# 2211B_SysArrosageAuto_MCU.net
KiCad netlist of a schematic drawn in Altium Designer
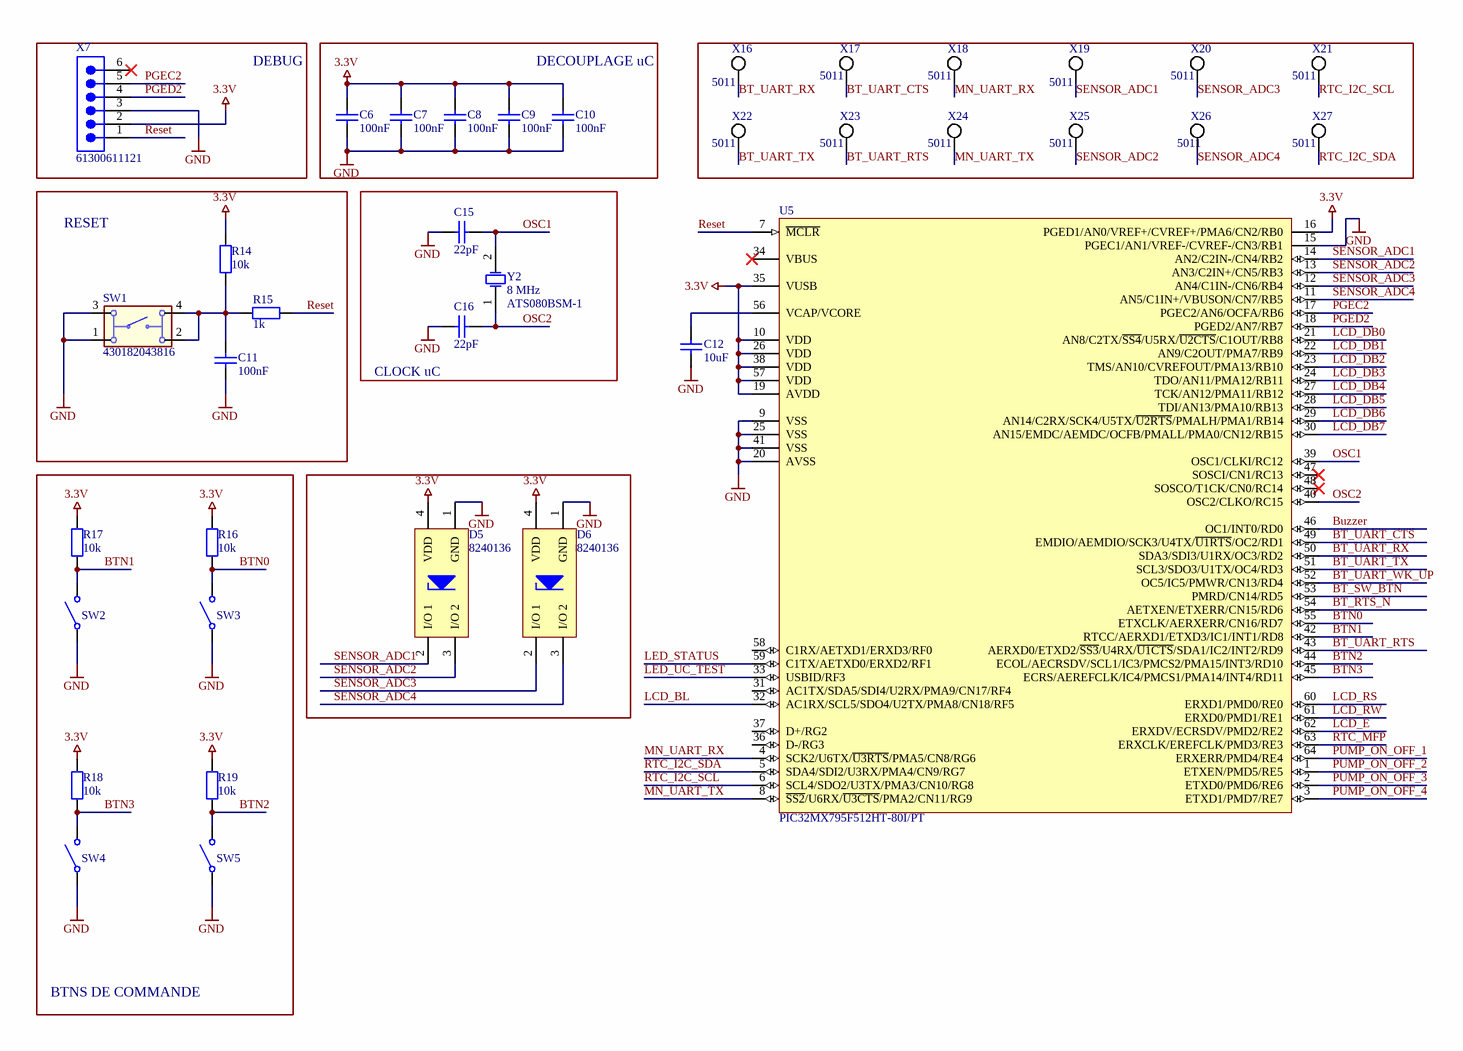
[diagram p0: 2211B_SysArrosageAuto_MCU.SchDoc, right]

(export (version "E")
  (design (tool "Eeschema 10.0.6"))
  (components
    (comp (ref "C6")
      (value "100nF")
      (footprint "CAPC2013X145X48NL20T23")
      (libsource (lib "Sys_Arossage") (part "Capacitor_Non-Polarized"))
    )
    (comp (ref "C7")
      (value "100nF")
      (footprint "CAPC2013X145X48NL20T23")
      (libsource (lib "Sys_Arossage") (part "Capacitor_Non-Polarized"))
    )
    (comp (ref "C8")
      (value "100nF")
      (footprint "CAPC2013X145X48NL20T23")
      (libsource (lib "Sys_Arossage") (part "Capacitor_Non-Polarized"))
    )
    (comp (ref "C9")
      (value "100nF")
      (footprint "CAPC2013X145X48NL20T23")
      (libsource (lib "Sys_Arossage") (part "Capacitor_Non-Polarized"))
    )
    (comp (ref "C10")
      (value "100nF")
      (footprint "CAPC2013X145X48NL20T23")
      (libsource (lib "Sys_Arossage") (part "Capacitor_Non-Polarized"))
    )
    (comp (ref "C11")
      (value "100nF")
      (footprint "CAPC2013X145X48NL20T23")
      (libsource (lib "Sys_Arossage") (part "Capacitor_Non-Polarized"))
    )
    (comp (ref "C12")
      (value "10uF")
      (footprint "CAPC2013X145X48NL20T23")
      (libsource (lib "Sys_Arossage") (part "Capacitor_Non-Polarized"))
    )
    (comp (ref "C15")
      (value "22pF")
      (footprint "CAPC2013X145X48NL20T23")
      (libsource (lib "Sys_Arossage") (part "Capacitor_Non-Polarized"))
    )
    (comp (ref "C16")
      (value "22pF")
      (footprint "CAPC2013X145X48NL20T23")
      (libsource (lib "Sys_Arossage") (part "Capacitor_Non-Polarized"))
    )
    (comp (ref "D5")
      (value "8240136")
      (footprint "WE-TVS_SOT143-4L")
      (libsource (lib "Sys_Arossage") (part "CMP-1486-00002-2"))
    )
    (comp (ref "D6")
      (value "8240136")
      (footprint "WE-TVS_SOT143-4L")
      (libsource (lib "Sys_Arossage") (part "CMP-1486-00002-2"))
    )
    (comp (ref "R14")
      (value "10k")
      (footprint "RESC2012X60N")
      (description "SMD Chip Resistor, 10 kOhm, ± 1%, 125 mW, 0805 [2012 Metric], Thick Film, General Purpose")
      (fields
        (field (name "MANUFACTURER") "Yageo")
        (field (name "MANUFACTURER PART NUMBER") "RC0805FR-0710KL")
      )
      (libsource (lib "Sys_Arossage") (part "R-SMD"))
    )
    (comp (ref "R15")
      (value "1k")
      (footprint "RESC2012X60N")
      (description "SMD Chip Resistor, 10 kOhm, ± 1%, 125 mW, 0805 [2012 Metric], Thick Film, General Purpose")
      (fields
        (field (name "MANUFACTURER") "Yageo")
        (field (name "MANUFACTURER PART NUMBER") "RC0805FR-0710KL")
      )
      (libsource (lib "") (part "R-SMD_1"))
    )
    (comp (ref "R16")
      (value "10k")
      (footprint "RESC2012X60N")
      (description "SMD Chip Resistor, 10 kOhm, ± 1%, 125 mW, 0805 [2012 Metric], Thick Film, General Purpose")
      (fields
        (field (name "MANUFACTURER") "Yageo")
        (field (name "MANUFACTURER PART NUMBER") "RC0805FR-0710KL")
      )
      (libsource (lib "Sys_Arossage") (part "R-SMD"))
    )
    (comp (ref "R17")
      (value "10k")
      (footprint "RESC2012X60N")
      (description "SMD Chip Resistor, 10 kOhm, ± 1%, 125 mW, 0805 [2012 Metric], Thick Film, General Purpose")
      (fields
        (field (name "MANUFACTURER") "Yageo")
        (field (name "MANUFACTURER PART NUMBER") "RC0805FR-0710KL")
      )
      (libsource (lib "Sys_Arossage") (part "R-SMD"))
    )
    (comp (ref "R18")
      (value "10k")
      (footprint "RESC2012X60N")
      (description "SMD Chip Resistor, 10 kOhm, ± 1%, 125 mW, 0805 [2012 Metric], Thick Film, General Purpose")
      (fields
        (field (name "MANUFACTURER") "Yageo")
        (field (name "MANUFACTURER PART NUMBER") "RC0805FR-0710KL")
      )
      (libsource (lib "Sys_Arossage") (part "R-SMD"))
    )
    (comp (ref "R19")
      (value "10k")
      (footprint "RESC2012X60N")
      (description "SMD Chip Resistor, 10 kOhm, ± 1%, 125 mW, 0805 [2012 Metric], Thick Film, General Purpose")
      (fields
        (field (name "MANUFACTURER") "Yageo")
        (field (name "MANUFACTURER PART NUMBER") "RC0805FR-0710KL")
      )
      (libsource (lib "Sys_Arossage") (part "R-SMD"))
    )
    (comp (ref "SW1")
      (value "430182043816")
      (footprint "SOIC_82043816_WRE-L")
      (description "Switch Tactile N.O. SPST Round Button Gull Wing 0.05A 12VDC 1000000Cycles 1.57N SMD Reel")
      (fields (field (name "MANUFACTURER") "Wurth Electronics"))
      (libsource (lib "Sys_Arossage") (part "SWITCH_SPST-NO"))
    )
    (comp (ref "SW2")
      (value "Single-Pole,Single-Throw Switch")
      (footprint "61300211121")
      (libsource (lib "Sys_Arossage") (part "SPST SW"))
    )
    (comp (ref "SW3")
      (value "Single-Pole,Single-Throw Switch")
      (footprint "61300211121")
      (libsource (lib "Sys_Arossage") (part "SPST SW"))
    )
    (comp (ref "SW4")
      (value "Single-Pole,Single-Throw Switch")
      (footprint "61300211121")
      (libsource (lib "Sys_Arossage") (part "SPST SW"))
    )
    (comp (ref "SW5")
      (value "Single-Pole,Single-Throw Switch")
      (footprint "61300211121")
      (libsource (lib "Sys_Arossage") (part "SPST SW"))
    )
    (comp (ref "U5")
      (value "PIC32MX795F512HT-80I/PT")
      (footprint "TQFP-PT64_L")
      (libsource (lib "Sys_Arossage") (part "CMP-0048-00048-2"))
    )
    (comp (ref "X7")
      (value "61300611121")
      (footprint "61300611121")
      (description "THT Vertical Pin Header WR-PHD, Pitch 2.54 mm, Single Row, 6 pins")
      (fields (field (name "MANUFACTURER") "Wurth Electronics"))
      (libsource (lib "Sys_Arossage") (part "CMP-1502-01068-2_1"))
    )
    (comp (ref "X16")
      (value "5011")
      (footprint "Keystone_5011")
      (fields (field (name "MANUFACTURER") "Keystone") (field (name "MANUFACTURER_1") "Keystone Electronics"))
      (libsource (lib "Sys_Arossage") (part "TEST_POINT_THT"))
    )
    (comp (ref "X17")
      (value "5011")
      (footprint "Keystone_5011")
      (fields (field (name "MANUFACTURER") "Keystone") (field (name "MANUFACTURER_1") "Keystone Electronics"))
      (libsource (lib "Sys_Arossage") (part "TEST_POINT_THT"))
    )
    (comp (ref "X18")
      (value "5011")
      (footprint "Keystone_5011")
      (fields (field (name "MANUFACTURER") "Keystone") (field (name "MANUFACTURER_1") "Keystone Electronics"))
      (libsource (lib "Sys_Arossage") (part "TEST_POINT_THT"))
    )
    (comp (ref "X19")
      (value "5011")
      (footprint "Keystone_5011")
      (fields (field (name "MANUFACTURER") "Keystone") (field (name "MANUFACTURER_1") "Keystone Electronics"))
      (libsource (lib "Sys_Arossage") (part "TEST_POINT_THT"))
    )
    (comp (ref "X20")
      (value "5011")
      (footprint "Keystone_5011")
      (fields (field (name "MANUFACTURER") "Keystone") (field (name "MANUFACTURER_1") "Keystone Electronics"))
      (libsource (lib "Sys_Arossage") (part "TEST_POINT_THT"))
    )
    (comp (ref "X21")
      (value "5011")
      (footprint "Keystone_5011")
      (fields (field (name "MANUFACTURER") "Keystone") (field (name "MANUFACTURER_1") "Keystone Electronics"))
      (libsource (lib "Sys_Arossage") (part "TEST_POINT_THT"))
    )
    (comp (ref "X22")
      (value "5011")
      (footprint "Keystone_5011")
      (fields (field (name "MANUFACTURER") "Keystone") (field (name "MANUFACTURER_1") "Keystone Electronics"))
      (libsource (lib "Sys_Arossage") (part "TEST_POINT_THT"))
    )
    (comp (ref "X23")
      (value "5011")
      (footprint "Keystone_5011")
      (fields (field (name "MANUFACTURER") "Keystone") (field (name "MANUFACTURER_1") "Keystone Electronics"))
      (libsource (lib "Sys_Arossage") (part "TEST_POINT_THT"))
    )
    (comp (ref "X24")
      (value "5011")
      (footprint "Keystone_5011")
      (fields (field (name "MANUFACTURER") "Keystone") (field (name "MANUFACTURER_1") "Keystone Electronics"))
      (libsource (lib "Sys_Arossage") (part "TEST_POINT_THT"))
    )
    (comp (ref "X25")
      (value "5011")
      (footprint "Keystone_5011")
      (fields (field (name "MANUFACTURER") "Keystone") (field (name "MANUFACTURER_1") "Keystone Electronics"))
      (libsource (lib "Sys_Arossage") (part "TEST_POINT_THT"))
    )
    (comp (ref "X26")
      (value "5011")
      (footprint "Keystone_5011")
      (fields (field (name "MANUFACTURER") "Keystone") (field (name "MANUFACTURER_1") "Keystone Electronics"))
      (libsource (lib "Sys_Arossage") (part "TEST_POINT_THT"))
    )
    (comp (ref "X27")
      (value "5011")
      (footprint "Keystone_5011")
      (fields (field (name "MANUFACTURER") "Keystone") (field (name "MANUFACTURER_1") "Keystone Electronics"))
      (libsource (lib "Sys_Arossage") (part "TEST_POINT_THT"))
    )
    (comp (ref "Y2")
      (value "8 MHz")
      (footprint "ATS080BSM-1")
      (description "Crystal 8MHz ±30ppm (Tol) ±50ppm (Stability) 18pF FUND 60Ohm 2-Pin HC-49/US SM SMD T/R")
      (fields
        (field (name "MANUFACTURER") "CTS")
        (field (name "MANUFACTURER PART NUMBER") "ATS080BSM-1")
        (field (name "SUPPLIER PART NUMBER 1") "ATS080BSM-1")
        (field (name "PUBLISHER") "Altium Limited")
      )
      (libsource (lib "Sys_Arossage") (part "XTAL"))
    )
  )
  (nets
    (net (code "1") (name "/BTN0") (class "Default")
      (node (ref "R16") (pin "1") (pinfunction "1_1") (pintype "passive"))
      (node (ref "SW3") (pin "2") (pinfunction "2_2") (pintype "passive"))
      (node (ref "U5") (pin "55") (pinfunction "ETXCLK/AERXERR/CN16/RD7_55") (pintype "bidirectional"))
    )
    (net (code "2") (name "/BTN1") (class "Default")
      (node (ref "R17") (pin "1") (pinfunction "1_1") (pintype "passive"))
      (node (ref "SW2") (pin "2") (pinfunction "2_2") (pintype "passive"))
      (node (ref "U5") (pin "42") (pinfunction "RTCC/AERXD1/ETXD3/IC1/INT1/RD8_42") (pintype "bidirectional"))
    )
    (net (code "3") (name "/BTN2") (class "Default")
      (node (ref "R19") (pin "1") (pinfunction "1_1") (pintype "passive"))
      (node (ref "SW5") (pin "2") (pinfunction "2_2") (pintype "passive"))
      (node (ref "U5") (pin "44") (pinfunction "ECOL/AECRSDV/SCL1/IC3/PMCS2/PMA15/INT3/RD10_44") (pintype "bidirectional"))
    )
    (net (code "4") (name "/BTN3") (class "Default")
      (node (ref "R18") (pin "1") (pinfunction "1_1") (pintype "passive"))
      (node (ref "SW4") (pin "2") (pinfunction "2_2") (pintype "passive"))
      (node (ref "U5") (pin "45") (pinfunction "ECRS/AEREFCLK/IC4/PMCS1/PMA14/INT4/RD11_45") (pintype "bidirectional"))
    )
    (net (code "5") (name "/BT_RTS_N") (class "Default")
      (node (ref "U5") (pin "54") (pinfunction "AETXEN/ETXERR/CN15/RD6_54") (pintype "bidirectional"))
    )
    (net (code "6") (name "/BT_SW_BTN") (class "Default")
      (node (ref "U5") (pin "53") (pinfunction "PMRD/CN14/RD5_53") (pintype "bidirectional"))
    )
    (net (code "7") (name "/BT_UART_CTS") (class "Default")
      (node (ref "U5") (pin "49") (pinfunction "EMDIO/AEMDIO/SCK3/U4TX/~{U1RTS}/OC2/RD1_49") (pintype "bidirectional"))
      (node (ref "X17") (pin "1") (pinfunction "TP_1") (pintype "passive"))
    )
    (net (code "8") (name "/BT_UART_RTS") (class "Default")
      (node (ref "U5") (pin "43") (pinfunction "AERXD0/ETXD2/~{SS3}/U4RX/~{U1CTS}/SDA1/IC2/INT2/RD9_43") (pintype "bidirectional"))
      (node (ref "X23") (pin "1") (pinfunction "TP_1") (pintype "passive"))
    )
    (net (code "9") (name "/BT_UART_RX") (class "Default")
      (node (ref "U5") (pin "50") (pinfunction "SDA3/SDI3/U1RX/OC3/RD2_50") (pintype "bidirectional"))
      (node (ref "X16") (pin "1") (pinfunction "TP_1") (pintype "passive"))
    )
    (net (code "10") (name "/BT_UART_TX") (class "Default")
      (node (ref "U5") (pin "51") (pinfunction "SCL3/SDO3/U1TX/OC4/RD3_51") (pintype "bidirectional"))
      (node (ref "X22") (pin "1") (pinfunction "TP_1") (pintype "passive"))
    )
    (net (code "11") (name "/BT_UART_WK_UP") (class "Default")
      (node (ref "U5") (pin "52") (pinfunction "OC5/IC5/PMWR/CN13/RD4_52") (pintype "bidirectional"))
    )
    (net (code "12") (name "/Buzzer") (class "Default")
      (node (ref "U5") (pin "46") (pinfunction "OC1/INT0/RD0_46") (pintype "bidirectional"))
    )
    (net (code "13") (name "/LCD_BL") (class "Default")
      (node (ref "U5") (pin "32") (pinfunction "AC1RX/SCL5/SDO4/U2TX/PMA8/CN18/RF5_32") (pintype "bidirectional"))
    )
    (net (code "14") (name "/LCD_DB0") (class "Default")
      (node (ref "U5") (pin "21") (pinfunction "AN8/C2TX/~{SS4}/U5RX/~{U2CTS}/C1OUT/RB8_21") (pintype "bidirectional"))
    )
    (net (code "15") (name "/LCD_DB1") (class "Default")
      (node (ref "U5") (pin "22") (pinfunction "AN9/C2OUT/PMA7/RB9_22") (pintype "bidirectional"))
    )
    (net (code "16") (name "/LCD_DB2") (class "Default")
      (node (ref "U5") (pin "23") (pinfunction "TMS/AN10/CVREFOUT/PMA13/RB10_23") (pintype "bidirectional"))
    )
    (net (code "17") (name "/LCD_DB3") (class "Default")
      (node (ref "U5") (pin "24") (pinfunction "TDO/AN11/PMA12/RB11_24") (pintype "bidirectional"))
    )
    (net (code "18") (name "/LCD_DB4") (class "Default")
      (node (ref "U5") (pin "27") (pinfunction "TCK/AN12/PMA11/RB12_27") (pintype "bidirectional"))
    )
    (net (code "19") (name "/LCD_DB5") (class "Default")
      (node (ref "U5") (pin "28") (pinfunction "TDI/AN13/PMA10/RB13_28") (pintype "bidirectional"))
    )
    (net (code "20") (name "/LCD_DB6") (class "Default")
      (node (ref "U5") (pin "29") (pinfunction "AN14/C2RX/SCK4/U5TX/~{U2RTS}/PMALH/PMA1/RB14_29") (pintype "bidirectional"))
    )
    (net (code "21") (name "/LCD_DB7") (class "Default")
      (node (ref "U5") (pin "30") (pinfunction "AN15/EMDC/AEMDC/OCFB/PMALL/PMA0/CN12/RB15_30") (pintype "bidirectional"))
    )
    (net (code "22") (name "/LCD_E") (class "Default")
      (node (ref "U5") (pin "62") (pinfunction "ERXDV/ECRSDV/PMD2/RE2_62") (pintype "bidirectional"))
    )
    (net (code "23") (name "/LCD_RS") (class "Default")
      (node (ref "U5") (pin "60") (pinfunction "ERXD1/PMD0/RE0_60") (pintype "bidirectional"))
    )
    (net (code "24") (name "/LCD_RW") (class "Default")
      (node (ref "U5") (pin "61") (pinfunction "ERXD0/PMD1/RE1_61") (pintype "bidirectional"))
    )
    (net (code "25") (name "/LED_STATUS") (class "Default")
      (node (ref "U5") (pin "59") (pinfunction "C1TX/AETXD0/ERXD2/RF1_59") (pintype "bidirectional"))
    )
    (net (code "26") (name "/LED_UC_TEST") (class "Default")
      (node (ref "U5") (pin "33") (pinfunction "USBID/RF3_33") (pintype "bidirectional"))
    )
    (net (code "27") (name "/MN_UART_RX") (class "Default")
      (node (ref "U5") (pin "4") (pinfunction "SCK2/U6TX/~{U3RTS}/PMA5/CN8/RG6_4") (pintype "bidirectional"))
      (node (ref "X18") (pin "1") (pinfunction "TP_1") (pintype "passive"))
    )
    (net (code "28") (name "/MN_UART_TX") (class "Default")
      (node (ref "U5") (pin "8") (pinfunction "~{SS2}/U6RX/~{U3CTS}/PMA2/CN11/RG9_8") (pintype "bidirectional"))
      (node (ref "X24") (pin "1") (pinfunction "TP_1") (pintype "passive"))
    )
    (net (code "29") (name "/OSC1") (class "Default")
      (node (ref "C15") (pin "2") (pinfunction "2_2") (pintype "passive"))
      (node (ref "U5") (pin "39") (pinfunction "OSC1/CLKI/RC12_39") (pintype "bidirectional"))
      (node (ref "Y2") (pin "2") (pinfunction "OSC2_2") (pintype "passive"))
    )
    (net (code "30") (name "/OSC2") (class "Default")
      (node (ref "C16") (pin "2") (pinfunction "2_2") (pintype "passive"))
      (node (ref "U5") (pin "40") (pinfunction "OSC2/CLKO/RC15_40") (pintype "bidirectional"))
      (node (ref "Y2") (pin "1") (pinfunction "OSC1_1") (pintype "passive"))
    )
    (net (code "31") (name "/PGEC2") (class "Default")
      (node (ref "U5") (pin "17") (pinfunction "PGEC2/AN6/OCFA/RB6_17") (pintype "bidirectional"))
      (node (ref "X7") (pin "5") (pinfunction "5_5") (pintype "passive"))
    )
    (net (code "32") (name "/PGED2") (class "Default")
      (node (ref "U5") (pin "18") (pinfunction "PGED2/AN7/RB7_18") (pintype "bidirectional"))
      (node (ref "X7") (pin "4") (pinfunction "4_4") (pintype "passive"))
    )
    (net (code "33") (name "/PUMP_ON_OFF_1") (class "Default")
      (node (ref "U5") (pin "64") (pinfunction "ERXERR/PMD4/RE4_64") (pintype "bidirectional"))
    )
    (net (code "34") (name "/PUMP_ON_OFF_2") (class "Default")
      (node (ref "U5") (pin "1") (pinfunction "ETXEN/PMD5/RE5_1") (pintype "bidirectional"))
    )
    (net (code "35") (name "/PUMP_ON_OFF_3") (class "Default")
      (node (ref "U5") (pin "2") (pinfunction "ETXD0/PMD6/RE6_2") (pintype "bidirectional"))
    )
    (net (code "36") (name "/PUMP_ON_OFF_4") (class "Default")
      (node (ref "U5") (pin "3") (pinfunction "ETXD1/PMD7/RE7_3") (pintype "bidirectional"))
    )
    (net (code "37") (name "/RTC_I2C_SCL") (class "Default")
      (node (ref "U5") (pin "6") (pinfunction "SCL4/SDO2/U3TX/PMA3/CN10/RG8_6") (pintype "bidirectional"))
      (node (ref "X21") (pin "1") (pinfunction "TP_1") (pintype "passive"))
    )
    (net (code "38") (name "/RTC_I2C_SDA") (class "Default")
      (node (ref "U5") (pin "5") (pinfunction "SDA4/SDI2/U3RX/PMA4/CN9/RG7_5") (pintype "bidirectional"))
      (node (ref "X27") (pin "1") (pinfunction "TP_1") (pintype "passive"))
    )
    (net (code "39") (name "/RTC_MFP") (class "Default")
      (node (ref "U5") (pin "63") (pinfunction "ERXCLK/EREFCLK/PMD3/RE3_63") (pintype "bidirectional"))
    )
    (net (code "40") (name "/Reset") (class "Default")
      (node (ref "R15") (pin "2") (pinfunction "2_2") (pintype "passive"))
      (node (ref "U5") (pin "7") (pinfunction "~{MCLR}_7") (pintype "input"))
      (node (ref "X7") (pin "1") (pinfunction "1_1") (pintype "passive"))
    )
    (net (code "41") (name "/SENSOR_ADC1") (class "Default")
      (node (ref "D5") (pin "2") (pinfunction "I/O_1_2") (pintype "passive"))
      (node (ref "U5") (pin "14") (pinfunction "AN2/C2IN-/CN4/RB2_14") (pintype "bidirectional"))
      (node (ref "X19") (pin "1") (pinfunction "TP_1") (pintype "passive"))
    )
    (net (code "42") (name "/SENSOR_ADC2") (class "Default")
      (node (ref "D5") (pin "3") (pinfunction "I/O_2_3") (pintype "passive"))
      (node (ref "U5") (pin "13") (pinfunction "AN3/C2IN+/CN5/RB3_13") (pintype "bidirectional"))
      (node (ref "X25") (pin "1") (pinfunction "TP_1") (pintype "passive"))
    )
    (net (code "43") (name "/SENSOR_ADC3") (class "Default")
      (node (ref "D6") (pin "2") (pinfunction "I/O_1_2") (pintype "passive"))
      (node (ref "U5") (pin "12") (pinfunction "AN4/C1IN-/CN6/RB4_12") (pintype "bidirectional"))
      (node (ref "X20") (pin "1") (pinfunction "TP_1") (pintype "passive"))
    )
    (net (code "44") (name "/SENSOR_ADC4") (class "Default")
      (node (ref "D6") (pin "3") (pinfunction "I/O_2_3") (pintype "passive"))
      (node (ref "U5") (pin "11") (pinfunction "AN5/C1IN+/VBUSON/CN7/RB5_11") (pintype "bidirectional"))
      (node (ref "X26") (pin "1") (pinfunction "TP_1") (pintype "passive"))
    )
    (net (code "45") (name "3.3V") (class "Default")
      (node (ref "C10") (pin "2") (pinfunction "2_2") (pintype "passive"))
      (node (ref "C6") (pin "2") (pinfunction "2_2") (pintype "passive"))
      (node (ref "C7") (pin "2") (pinfunction "2_2") (pintype "passive"))
      (node (ref "C8") (pin "2") (pinfunction "2_2") (pintype "passive"))
      (node (ref "C9") (pin "2") (pinfunction "2_2") (pintype "passive"))
      (node (ref "D5") (pin "4") (pinfunction "VDD_4") (pintype "passive"))
      (node (ref "D6") (pin "4") (pinfunction "VDD_4") (pintype "passive"))
      (node (ref "R14") (pin "2") (pinfunction "2_2") (pintype "passive"))
      (node (ref "R16") (pin "2") (pinfunction "2_2") (pintype "passive"))
      (node (ref "R17") (pin "2") (pinfunction "2_2") (pintype "passive"))
      (node (ref "R18") (pin "2") (pinfunction "2_2") (pintype "passive"))
      (node (ref "R19") (pin "2") (pinfunction "2_2") (pintype "passive"))
      (node (ref "U5") (pin "10") (pinfunction "VDD_10") (pintype "passive"))
      (node (ref "U5") (pin "16") (pinfunction "PGED1/AN0/VREF+/CVREF+/PMA6/CN2/RB0_16") (pintype "power_in"))
      (node (ref "U5") (pin "19") (pinfunction "AVDD_19") (pintype "passive"))
      (node (ref "U5") (pin "26") (pinfunction "VDD_26") (pintype "passive"))
      (node (ref "U5") (pin "35") (pinfunction "VUSB_35") (pintype "passive"))
      (node (ref "U5") (pin "38") (pinfunction "VDD_38") (pintype "passive"))
      (node (ref "U5") (pin "57") (pinfunction "VDD_57") (pintype "passive"))
      (node (ref "X7") (pin "2") (pinfunction "2_2") (pintype "passive"))
    )
    (net (code "46") (name "GND") (class "Default")
      (node (ref "C10") (pin "1") (pinfunction "1_1") (pintype "passive"))
      (node (ref "C11") (pin "1") (pinfunction "1_1") (pintype "passive"))
      (node (ref "C12") (pin "1") (pinfunction "1_1") (pintype "passive"))
      (node (ref "C15") (pin "1") (pinfunction "1_1") (pintype "passive"))
      (node (ref "C16") (pin "1") (pinfunction "1_1") (pintype "passive"))
      (node (ref "C6") (pin "1") (pinfunction "1_1") (pintype "passive"))
      (node (ref "C7") (pin "1") (pinfunction "1_1") (pintype "passive"))
      (node (ref "C8") (pin "1") (pinfunction "1_1") (pintype "passive"))
      (node (ref "C9") (pin "1") (pinfunction "1_1") (pintype "passive"))
      (node (ref "D5") (pin "1") (pinfunction "GND_1") (pintype "passive"))
      (node (ref "D6") (pin "1") (pinfunction "GND_1") (pintype "passive"))
      (node (ref "SW1") (pin "1") (pinfunction "1_1") (pintype "passive"))
      (node (ref "SW1") (pin "3") (pinfunction "3_3") (pintype "passive"))
      (node (ref "SW2") (pin "1") (pinfunction "1_1") (pintype "passive"))
      (node (ref "SW3") (pin "1") (pinfunction "1_1") (pintype "passive"))
      (node (ref "SW4") (pin "1") (pinfunction "1_1") (pintype "passive"))
      (node (ref "SW5") (pin "1") (pinfunction "1_1") (pintype "passive"))
      (node (ref "U5") (pin "15") (pinfunction "PGEC1/AN1/VREF-/CVREF-/CN3/RB1_15") (pintype "power_in"))
      (node (ref "U5") (pin "20") (pinfunction "AVSS_20") (pintype "passive"))
      (node (ref "U5") (pin "25") (pinfunction "VSS_25") (pintype "passive"))
      (node (ref "U5") (pin "41") (pinfunction "VSS_41") (pintype "passive"))
      (node (ref "U5") (pin "9") (pinfunction "VSS_9") (pintype "passive"))
      (node (ref "X7") (pin "3") (pinfunction "3_3") (pintype "passive"))
    )
    (net (code "47") (name "Net-(C11-Pad2)") (class "Default")
      (node (ref "C11") (pin "2") (pinfunction "2_2") (pintype "passive"))
      (node (ref "R14") (pin "1") (pinfunction "1_1") (pintype "passive"))
      (node (ref "R15") (pin "1") (pinfunction "1_1") (pintype "passive"))
      (node (ref "SW1") (pin "2") (pinfunction "2_2") (pintype "passive"))
      (node (ref "SW1") (pin "4") (pinfunction "4_4") (pintype "passive"))
    )
    (net (code "48") (name "Net-(U5-VCAP{slash}VCORE)") (class "Default")
      (node (ref "C12") (pin "2") (pinfunction "2_2") (pintype "passive"))
      (node (ref "U5") (pin "56") (pinfunction "VCAP/VCORE_56") (pintype "passive"))
    )
    (net (code "49") (name "unconnected-(U5-AC1TX{slash}SDA5{slash}SDI4{slash}U2RX{slash}PMA9{slash}CN17{slash}RF4-Pad31)") (class "Default")
      (node (ref "U5") (pin "31") (pinfunction "AC1TX/SDA5/SDI4/U2RX/PMA9/CN17/RF4_31") (pintype "bidirectional"))
    )
    (net (code "50") (name "unconnected-(U5-C1RX{slash}AETXD1{slash}ERXD3{slash}RF0-Pad58)") (class "Default")
      (node (ref "U5") (pin "58") (pinfunction "C1RX/AETXD1/ERXD3/RF0_58") (pintype "bidirectional"))
    )
    (net (code "51") (name "unconnected-(U5-D+{slash}RG2-Pad37)") (class "Default")
      (node (ref "U5") (pin "37") (pinfunction "D+/RG2_37") (pintype "bidirectional"))
    )
    (net (code "52") (name "unconnected-(U5-D-{slash}RG3-Pad36)") (class "Default")
      (node (ref "U5") (pin "36") (pinfunction "D-/RG3_36") (pintype "bidirectional"))
    )
    (net (code "53") (name "unconnected-(U5-SOSCI{slash}CN1{slash}RC13-Pad47)") (class "Default")
      (node (ref "U5") (pin "47") (pinfunction "SOSCI/CN1/RC13_47") (pintype "bidirectional+no_connect"))
    )
    (net (code "54") (name "unconnected-(U5-SOSCO{slash}T1CK{slash}CN0{slash}RC14-Pad48)") (class "Default")
      (node (ref "U5") (pin "48") (pinfunction "SOSCO/T1CK/CN0/RC14_48") (pintype "bidirectional+no_connect"))
    )
    (net (code "55") (name "unconnected-(U5-VBUS-Pad34)") (class "Default")
      (node (ref "U5") (pin "34") (pinfunction "VBUS_34") (pintype "passive+no_connect"))
    )
    (net (code "56") (name "unconnected-(X7-Pad6)") (class "Default")
      (node (ref "X7") (pin "6") (pinfunction "6_6") (pintype "passive+no_connect"))
    )
  )
)
